# main.net
KiCad netlist of a schematic drawn in EAGLE
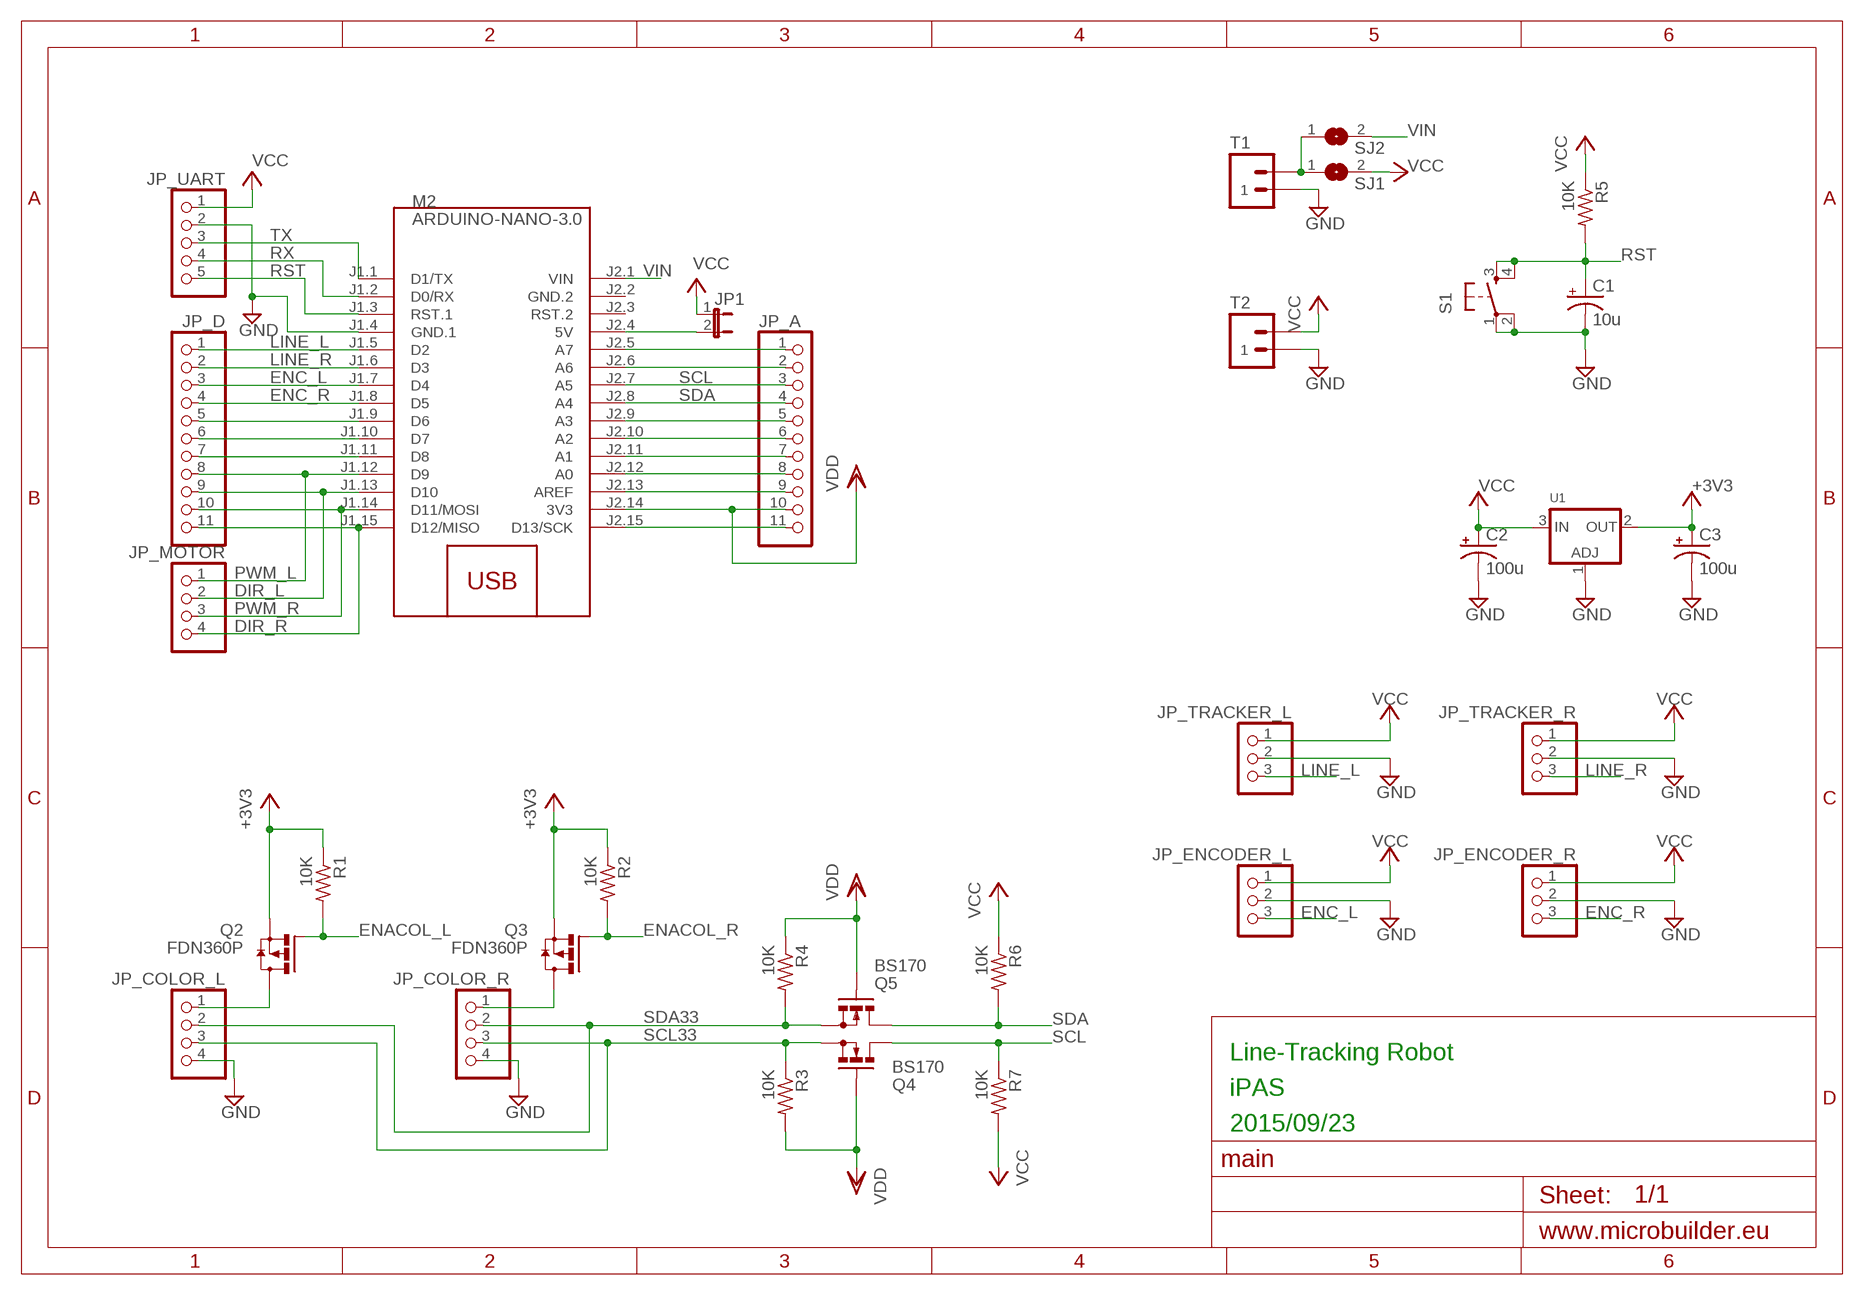
[diagram p0: schematic, sheet 1]

(export (version "E")
  (design (tool "Eeschema 10.0.6"))
  (components
    (comp (ref "C1")
      (value "10u")
      (footprint "eagle-import:RCL_E2,5-6")
      (libsource (lib "eagle-import") (part "RCL_CPOL-USE2.5-6"))
    )
    (comp (ref "C2")
      (value "100u")
      (footprint "eagle-import:RCL_E2,5-6")
      (libsource (lib "eagle-import") (part "RCL_CPOL-USE2.5-6"))
    )
    (comp (ref "C3")
      (value "100u")
      (footprint "eagle-import:RCL_E2,5-6")
      (libsource (lib "eagle-import") (part "RCL_CPOL-USE2.5-6"))
    )
    (comp (ref "JP1")
      (value "JUMPER2")
      (footprint "eagle-import:JUMPER2")
      (libsource (lib "eagle-import") (part "JUMPER2"))
    )
    (comp (ref "JP_A")
      (value "HEADER-1X11")
      (footprint "eagle-import:1X11_ROUND")
      (libsource (lib "eagle-import") (part "HEADER-1X11"))
    )
    (comp (ref "JP_COLOR_L")
      (value "HEADER-1X4ROUND")
      (footprint "eagle-import:1X04_ROUND")
      (libsource (lib "eagle-import") (part "HEADER-1X4ROUND"))
    )
    (comp (ref "JP_COLOR_R")
      (value "HEADER-1X4ROUND")
      (footprint "eagle-import:1X04_ROUND")
      (libsource (lib "eagle-import") (part "HEADER-1X4ROUND"))
    )
    (comp (ref "JP_D")
      (value "HEADER-1X11")
      (footprint "eagle-import:1X11_ROUND")
      (libsource (lib "eagle-import") (part "HEADER-1X11"))
    )
    (comp (ref "JP_ENCODER_L")
      (value "HEADER-1X3ROUND")
      (footprint "eagle-import:1X03_ROUND")
      (libsource (lib "eagle-import") (part "HEADER-1X3ROUND"))
    )
    (comp (ref "JP_ENCODER_R")
      (value "HEADER-1X3ROUND")
      (footprint "eagle-import:1X03_ROUND")
      (libsource (lib "eagle-import") (part "HEADER-1X3ROUND"))
    )
    (comp (ref "JP_MOTOR")
      (value "HEADER-1X4ROUND")
      (footprint "eagle-import:1X04_ROUND")
      (libsource (lib "eagle-import") (part "HEADER-1X4ROUND"))
    )
    (comp (ref "JP_TRACKER_L")
      (value "HEADER-1X3ROUND")
      (footprint "eagle-import:1X03_ROUND")
      (libsource (lib "eagle-import") (part "HEADER-1X3ROUND"))
    )
    (comp (ref "JP_TRACKER_R")
      (value "HEADER-1X3ROUND")
      (footprint "eagle-import:1X03_ROUND")
      (libsource (lib "eagle-import") (part "HEADER-1X3ROUND"))
    )
    (comp (ref "JP_UART")
      (value "HEADER-1X5ROUND")
      (footprint "eagle-import:1X05_ROUND")
      (libsource (lib "eagle-import") (part "HEADER-1X5ROUND"))
    )
    (comp (ref "M2")
      (value "ARDUINO-NANO-3.0")
      (footprint "eagle-import:ARDUINO-NANO-3.0")
      (libsource (lib "eagle-import") (part "ARDUINO-NANO-3.0"))
    )
    (comp (ref "Q2")
      (value "FDN360P")
      (footprint "eagle-import:SUPER-SOT3")
      (libsource (lib "eagle-import") (part "FDN360P"))
    )
    (comp (ref "Q3")
      (value "FDN360P")
      (footprint "eagle-import:SUPER-SOT3")
      (libsource (lib "eagle-import") (part "FDN360P"))
    )
    (comp (ref "Q4")
      (value "BS170")
      (footprint "eagle-import:TO92-")
      (libsource (lib "eagle-import") (part "BS170"))
    )
    (comp (ref "Q5")
      (value "BS170")
      (footprint "eagle-import:TO92-")
      (libsource (lib "eagle-import") (part "BS170"))
    )
    (comp (ref "R1")
      (value "10K")
      (footprint "eagle-import:RCL_0204_5")
      (libsource (lib "eagle-import") (part "RCL_R-US0204/5"))
    )
    (comp (ref "R2")
      (value "10K")
      (footprint "eagle-import:RCL_0204_5")
      (libsource (lib "eagle-import") (part "RCL_R-US0204/5"))
    )
    (comp (ref "R3")
      (value "10K")
      (footprint "eagle-import:RCL_0204_5")
      (libsource (lib "eagle-import") (part "RCL_R-US0204/5"))
    )
    (comp (ref "R4")
      (value "10K")
      (footprint "eagle-import:RCL_0204_5")
      (libsource (lib "eagle-import") (part "RCL_R-US0204/5"))
    )
    (comp (ref "R5")
      (value "10K")
      (footprint "eagle-import:RCL_0204_5")
      (libsource (lib "eagle-import") (part "RCL_R-US0204/5"))
    )
    (comp (ref "R6")
      (value "10K")
      (footprint "eagle-import:RCL_0204_5")
      (libsource (lib "eagle-import") (part "RCL_R-US0204/5"))
    )
    (comp (ref "R7")
      (value "10K")
      (footprint "eagle-import:RCL_0204_5")
      (libsource (lib "eagle-import") (part "RCL_R-US0204/5"))
    )
    (comp (ref "S1")
      (value "SWITCH-TACT_DTS-6")
      (footprint "eagle-import:SWITCH-TACT_DTS-6")
      (libsource (lib "eagle-import") (part "SWITCH-TACT_DTS-6"))
    )
    (comp (ref "SJ1")
      (value "SOLDERJUMPERREFLOW")
      (footprint "eagle-import:SOLDERJUMPER_REFLOW")
      (libsource (lib "eagle-import") (part "SOLDERJUMPERREFLOW"))
    )
    (comp (ref "SJ2")
      (value "SOLDERJUMPERREFLOW")
      (footprint "eagle-import:SOLDERJUMPER_REFLOW")
      (libsource (lib "eagle-import") (part "SOLDERJUMPERREFLOW"))
    )
    (comp (ref "T1")
      (value "ST02-3.81MM")
      (footprint "eagle-import:DG381-02P")
      (libsource (lib "eagle-import") (part "ST02-3.81MM"))
    )
    (comp (ref "T2")
      (value "ST02-3.81MM")
      (footprint "eagle-import:DG381-02P")
      (libsource (lib "eagle-import") (part "ST02-3.81MM"))
    )
    (comp (ref "U1")
      (value "LM1117SOT223-REFLOW")
      (footprint "eagle-import:SOT223-R")
      (libsource (lib "eagle-import") (part "LM1117SOT223-REFLOW"))
    )
  )
  (nets
    (net (code "1") (name "+3V3") (class "Default")
      (node (ref "C3") (pin "+") (pinfunction "+_+") (pintype "passive"))
      (node (ref "Q2") (pin "2") (pinfunction "S_2") (pintype "passive"))
      (node (ref "Q3") (pin "2") (pinfunction "S_2") (pintype "passive"))
      (node (ref "R1") (pin "1") (pinfunction "1_1") (pintype "passive"))
      (node (ref "R2") (pin "1") (pinfunction "1_1") (pintype "passive"))
      (node (ref "U1") (pin "2") (pinfunction "OUT_2") (pintype "passive"))
    )
    (net (code "2") (name "/DIR_L") (class "Default")
      (node (ref "JP_D") (pin "9") (pinfunction "9_9") (pintype "passive"))
      (node (ref "JP_MOTOR") (pin "2") (pinfunction "2_2") (pintype "passive"))
      (node (ref "M2") (pin "J1.13") (pinfunction "D10_J1.13") (pintype "bidirectional"))
    )
    (net (code "3") (name "/DIR_R") (class "Default")
      (node (ref "JP_D") (pin "11") (pinfunction "11_11") (pintype "passive"))
      (node (ref "JP_MOTOR") (pin "4") (pinfunction "4_4") (pintype "passive"))
      (node (ref "M2") (pin "J1.15") (pinfunction "D12/MISO_J1.15") (pintype "bidirectional"))
    )
    (net (code "4") (name "/ENACOL_L") (class "Default")
      (node (ref "Q2") (pin "1") (pinfunction "G_1") (pintype "passive"))
      (node (ref "R1") (pin "2") (pinfunction "2_2") (pintype "passive"))
    )
    (net (code "5") (name "/ENACOL_R") (class "Default")
      (node (ref "Q3") (pin "1") (pinfunction "G_1") (pintype "passive"))
      (node (ref "R2") (pin "2") (pinfunction "2_2") (pintype "passive"))
    )
    (net (code "6") (name "/ENC_L") (class "Default")
      (node (ref "JP_D") (pin "3") (pinfunction "3_3") (pintype "passive"))
      (node (ref "JP_ENCODER_L") (pin "3") (pinfunction "3_3") (pintype "passive"))
      (node (ref "M2") (pin "J1.7") (pinfunction "D4_J1.7") (pintype "bidirectional"))
    )
    (net (code "7") (name "/ENC_R") (class "Default")
      (node (ref "JP_D") (pin "4") (pinfunction "4_4") (pintype "passive"))
      (node (ref "JP_ENCODER_R") (pin "3") (pinfunction "3_3") (pintype "passive"))
      (node (ref "M2") (pin "J1.8") (pinfunction "D5_J1.8") (pintype "bidirectional"))
    )
    (net (code "8") (name "/GND.2") (class "Default")
      (node (ref "M2") (pin "J2.2") (pinfunction "GND.2_J2.2") (pintype "power_in"))
    )
    (net (code "9") (name "/LINE_L") (class "Default")
      (node (ref "JP_D") (pin "1") (pinfunction "1_1") (pintype "passive"))
      (node (ref "JP_TRACKER_L") (pin "3") (pinfunction "3_3") (pintype "passive"))
      (node (ref "M2") (pin "J1.5") (pinfunction "D2_J1.5") (pintype "bidirectional"))
    )
    (net (code "10") (name "/LINE_R") (class "Default")
      (node (ref "JP_D") (pin "2") (pinfunction "2_2") (pintype "passive"))
      (node (ref "JP_TRACKER_R") (pin "3") (pinfunction "3_3") (pintype "passive"))
      (node (ref "M2") (pin "J1.6") (pinfunction "D3_J1.6") (pintype "bidirectional"))
    )
    (net (code "11") (name "/PWM_L") (class "Default")
      (node (ref "JP_D") (pin "8") (pinfunction "8_8") (pintype "passive"))
      (node (ref "JP_MOTOR") (pin "1") (pinfunction "1_1") (pintype "passive"))
      (node (ref "M2") (pin "J1.12") (pinfunction "D9_J1.12") (pintype "bidirectional"))
    )
    (net (code "12") (name "/PWM_R") (class "Default")
      (node (ref "JP_D") (pin "10") (pinfunction "10_10") (pintype "passive"))
      (node (ref "JP_MOTOR") (pin "3") (pinfunction "3_3") (pintype "passive"))
      (node (ref "M2") (pin "J1.14") (pinfunction "D11/MOSI_J1.14") (pintype "bidirectional"))
    )
    (net (code "13") (name "/RST") (class "Default")
      (node (ref "C1") (pin "+") (pinfunction "+_+") (pintype "passive"))
      (node (ref "JP_UART") (pin "5") (pinfunction "5_5") (pintype "passive"))
      (node (ref "M2") (pin "J1.3") (pinfunction "RST.1_J1.3") (pintype "bidirectional"))
      (node (ref "R5") (pin "2") (pinfunction "2_2") (pintype "passive"))
      (node (ref "S1") (pin "3") (pinfunction "3_3") (pintype "passive"))
      (node (ref "S1") (pin "4") (pinfunction "4_4") (pintype "passive"))
    )
    (net (code "14") (name "/RX") (class "Default")
      (node (ref "JP_UART") (pin "4") (pinfunction "4_4") (pintype "passive"))
      (node (ref "M2") (pin "J1.2") (pinfunction "D0/RX_J1.2") (pintype "bidirectional"))
    )
    (net (code "15") (name "/SCL") (class "Default")
      (node (ref "JP_A") (pin "3") (pinfunction "3_3") (pintype "passive"))
      (node (ref "M2") (pin "J2.7") (pinfunction "A5_J2.7") (pintype "bidirectional"))
      (node (ref "Q4") (pin "1") (pinfunction "D_1") (pintype "passive"))
      (node (ref "R7") (pin "1") (pinfunction "1_1") (pintype "passive"))
    )
    (net (code "16") (name "/SCL33") (class "Default")
      (node (ref "JP_COLOR_L") (pin "3") (pinfunction "3_3") (pintype "passive"))
      (node (ref "JP_COLOR_R") (pin "3") (pinfunction "3_3") (pintype "passive"))
      (node (ref "Q4") (pin "3") (pinfunction "S_3") (pintype "passive"))
      (node (ref "R3") (pin "1") (pinfunction "1_1") (pintype "passive"))
    )
    (net (code "17") (name "/SDA") (class "Default")
      (node (ref "JP_A") (pin "4") (pinfunction "4_4") (pintype "passive"))
      (node (ref "M2") (pin "J2.8") (pinfunction "A4_J2.8") (pintype "bidirectional"))
      (node (ref "Q5") (pin "1") (pinfunction "D_1") (pintype "passive"))
      (node (ref "R6") (pin "2") (pinfunction "2_2") (pintype "passive"))
    )
    (net (code "18") (name "/SDA33") (class "Default")
      (node (ref "JP_COLOR_L") (pin "2") (pinfunction "2_2") (pintype "passive"))
      (node (ref "JP_COLOR_R") (pin "2") (pinfunction "2_2") (pintype "passive"))
      (node (ref "Q5") (pin "3") (pinfunction "S_3") (pintype "passive"))
      (node (ref "R4") (pin "2") (pinfunction "2_2") (pintype "passive"))
    )
    (net (code "19") (name "/TX") (class "Default")
      (node (ref "JP_UART") (pin "3") (pinfunction "3_3") (pintype "passive"))
      (node (ref "M2") (pin "J1.1") (pinfunction "D1/TX_J1.1") (pintype "bidirectional"))
    )
    (net (code "20") (name "/VIN") (class "Default")
      (node (ref "M2") (pin "J2.1") (pinfunction "VIN_J2.1") (pintype "power_in"))
      (node (ref "SJ2") (pin "2") (pinfunction "2_2") (pintype "passive"))
    )
    (net (code "21") (name "GND") (class "Default")
      (node (ref "C1") (pin "-") (pinfunction "-_-") (pintype "passive"))
      (node (ref "C2") (pin "-") (pinfunction "-_-") (pintype "passive"))
      (node (ref "C3") (pin "-") (pinfunction "-_-") (pintype "passive"))
      (node (ref "JP_COLOR_L") (pin "4") (pinfunction "4_4") (pintype "passive"))
      (node (ref "JP_COLOR_R") (pin "4") (pinfunction "4_4") (pintype "passive"))
      (node (ref "JP_ENCODER_L") (pin "2") (pinfunction "2_2") (pintype "passive"))
      (node (ref "JP_ENCODER_R") (pin "2") (pinfunction "2_2") (pintype "passive"))
      (node (ref "JP_TRACKER_L") (pin "2") (pinfunction "2_2") (pintype "passive"))
      (node (ref "JP_TRACKER_R") (pin "2") (pinfunction "2_2") (pintype "passive"))
      (node (ref "JP_UART") (pin "2") (pinfunction "2_2") (pintype "passive"))
      (node (ref "M2") (pin "J1.4") (pinfunction "GND.1_J1.4") (pintype "power_in"))
      (node (ref "S1") (pin "1") (pinfunction "1_1") (pintype "passive"))
      (node (ref "S1") (pin "2") (pinfunction "2_2") (pintype "passive"))
      (node (ref "T1") (pin "1") (pinfunction "1_1") (pintype "passive"))
      (node (ref "T2") (pin "1") (pinfunction "1_1") (pintype "passive"))
      (node (ref "U1") (pin "1") (pinfunction "ADJ_1") (pintype "input"))
    )
    (net (code "22") (name "Net-(M2-5V)") (class "Default")
      (node (ref "JP1") (pin "2") (pinfunction "2_2") (pintype "passive"))
      (node (ref "M2") (pin "J2.4") (pinfunction "5V_J2.4") (pintype "power_in"))
    )
    (net (code "23") (name "Net-(M2-A0)") (class "Default")
      (node (ref "JP_A") (pin "8") (pinfunction "8_8") (pintype "passive"))
      (node (ref "M2") (pin "J2.12") (pinfunction "A0_J2.12") (pintype "bidirectional"))
    )
    (net (code "24") (name "Net-(M2-A1)") (class "Default")
      (node (ref "JP_A") (pin "7") (pinfunction "7_7") (pintype "passive"))
      (node (ref "M2") (pin "J2.11") (pinfunction "A1_J2.11") (pintype "bidirectional"))
    )
    (net (code "25") (name "Net-(M2-A2)") (class "Default")
      (node (ref "JP_A") (pin "6") (pinfunction "6_6") (pintype "passive"))
      (node (ref "M2") (pin "J2.10") (pinfunction "A2_J2.10") (pintype "bidirectional"))
    )
    (net (code "26") (name "Net-(M2-A3)") (class "Default")
      (node (ref "JP_A") (pin "5") (pinfunction "5_5") (pintype "passive"))
      (node (ref "M2") (pin "J2.9") (pinfunction "A3_J2.9") (pintype "bidirectional"))
    )
    (net (code "27") (name "Net-(M2-A6)") (class "Default")
      (node (ref "JP_A") (pin "2") (pinfunction "2_2") (pintype "passive"))
      (node (ref "M2") (pin "J2.6") (pinfunction "A6_J2.6") (pintype "bidirectional"))
    )
    (net (code "28") (name "Net-(M2-A7)") (class "Default")
      (node (ref "JP_A") (pin "1") (pinfunction "1_1") (pintype "passive"))
      (node (ref "M2") (pin "J2.5") (pinfunction "A7_J2.5") (pintype "bidirectional"))
    )
    (net (code "29") (name "Net-(M2-AREF)") (class "Default")
      (node (ref "JP_A") (pin "9") (pinfunction "9_9") (pintype "passive"))
      (node (ref "M2") (pin "J2.13") (pinfunction "AREF_J2.13") (pintype "bidirectional"))
    )
    (net (code "30") (name "Net-(M2-D6)") (class "Default")
      (node (ref "JP_D") (pin "5") (pinfunction "5_5") (pintype "passive"))
      (node (ref "M2") (pin "J1.9") (pinfunction "D6_J1.9") (pintype "bidirectional"))
    )
    (net (code "31") (name "Net-(M2-D7)") (class "Default")
      (node (ref "JP_D") (pin "6") (pinfunction "6_6") (pintype "passive"))
      (node (ref "M2") (pin "J1.10") (pinfunction "D7_J1.10") (pintype "bidirectional"))
    )
    (net (code "32") (name "Net-(M2-D8)") (class "Default")
      (node (ref "JP_D") (pin "7") (pinfunction "7_7") (pintype "passive"))
      (node (ref "M2") (pin "J1.11") (pinfunction "D8_J1.11") (pintype "bidirectional"))
    )
    (net (code "33") (name "Net-(M2-D13{slash}SCK)") (class "Default")
      (node (ref "JP_A") (pin "11") (pinfunction "11_11") (pintype "passive"))
      (node (ref "M2") (pin "J2.15") (pinfunction "D13/SCK_J2.15") (pintype "bidirectional"))
    )
    (net (code "34") (name "Net-(Q2-D)") (class "Default")
      (node (ref "JP_COLOR_L") (pin "1") (pinfunction "1_1") (pintype "passive"))
      (node (ref "Q2") (pin "3") (pinfunction "D_3") (pintype "passive"))
    )
    (net (code "35") (name "Net-(Q3-D)") (class "Default")
      (node (ref "JP_COLOR_R") (pin "1") (pinfunction "1_1") (pintype "passive"))
      (node (ref "Q3") (pin "3") (pinfunction "D_3") (pintype "passive"))
    )
    (net (code "36") (name "Net-(SJ1-Pad1)") (class "Default")
      (node (ref "SJ1") (pin "1") (pinfunction "1_1") (pintype "passive"))
      (node (ref "SJ2") (pin "1") (pinfunction "1_1") (pintype "passive"))
      (node (ref "T1") (pin "2") (pinfunction "2_2") (pintype "passive"))
    )
    (net (code "37") (name "VCC") (class "Default")
      (node (ref "C2") (pin "+") (pinfunction "+_+") (pintype "passive"))
      (node (ref "JP1") (pin "1") (pinfunction "1_1") (pintype "passive"))
      (node (ref "JP_ENCODER_L") (pin "1") (pinfunction "1_1") (pintype "passive"))
      (node (ref "JP_ENCODER_R") (pin "1") (pinfunction "1_1") (pintype "passive"))
      (node (ref "JP_TRACKER_L") (pin "1") (pinfunction "1_1") (pintype "passive"))
      (node (ref "JP_TRACKER_R") (pin "1") (pinfunction "1_1") (pintype "passive"))
      (node (ref "JP_UART") (pin "1") (pinfunction "1_1") (pintype "passive"))
      (node (ref "R5") (pin "1") (pinfunction "1_1") (pintype "passive"))
      (node (ref "R6") (pin "1") (pinfunction "1_1") (pintype "passive"))
      (node (ref "R7") (pin "2") (pinfunction "2_2") (pintype "passive"))
      (node (ref "SJ1") (pin "2") (pinfunction "2_2") (pintype "passive"))
      (node (ref "T2") (pin "2") (pinfunction "2_2") (pintype "passive"))
      (node (ref "U1") (pin "3") (pinfunction "IN_3") (pintype "input"))
    )
    (net (code "38") (name "VDD") (class "Default")
      (node (ref "JP_A") (pin "10") (pinfunction "10_10") (pintype "passive"))
      (node (ref "M2") (pin "J2.14") (pinfunction "3V3_J2.14") (pintype "power_in"))
      (node (ref "Q4") (pin "2") (pinfunction "G_2") (pintype "passive"))
      (node (ref "Q5") (pin "2") (pinfunction "G_2") (pintype "passive"))
      (node (ref "R3") (pin "2") (pinfunction "2_2") (pintype "passive"))
      (node (ref "R4") (pin "1") (pinfunction "1_1") (pintype "passive"))
    )
    (net (code "39") (name "unconnected-(M2-RST.2-PadJ2.3)") (class "Default")
      (node (ref "M2") (pin "J2.3") (pinfunction "RST.2_J2.3") (pintype "bidirectional"))
    )
  )
)
